# FinalPCBLayoutPoV.net
KiCad netlist of a schematic drawn in EAGLE
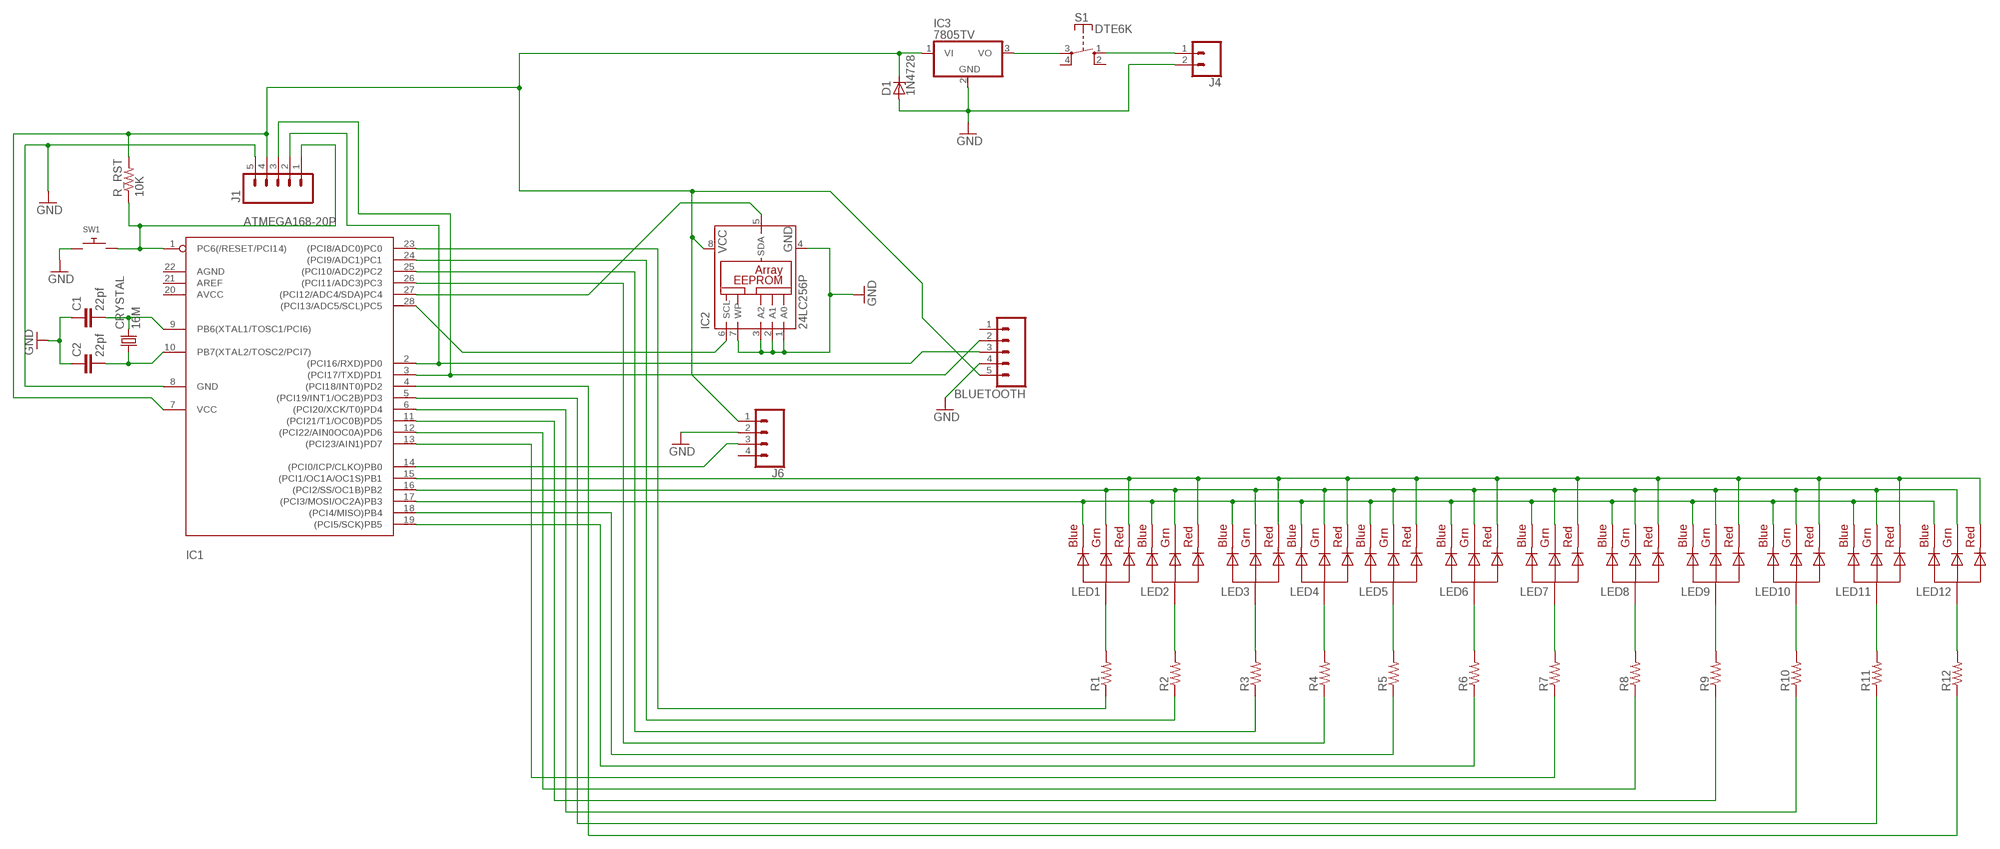
[diagram p0: schematic, sheet 1]

(export (version "E")
  (design (tool "Eeschema 10.0.6"))
  (components
    (comp (ref "BLUETOOTH")
      (value "M05SCREW")
      (footprint "eagle-import:SCREWTERMINAL-3.5MM-5")
      (libsource (lib "eagle-import") (part "M05SCREW"))
    )
    (comp (ref "C1")
      (value "22pf")
      (footprint "eagle-import:C025-060X050")
      (libsource (lib "eagle-import") (part "C-EU025-060X050"))
    )
    (comp (ref "C2")
      (value "22pf")
      (footprint "eagle-import:C025-060X050")
      (libsource (lib "eagle-import") (part "C-EU025-060X050"))
    )
    (comp (ref "CRYSTAL")
      (value "16M")
      (footprint "eagle-import:HC49_S")
      (libsource (lib "eagle-import") (part "CRYSTALHC49S"))
    )
    (comp (ref "D1")
      (value "1N4728")
      (footprint "eagle-import:DO41Z10")
      (libsource (lib "eagle-import") (part "1N4728"))
    )
    (comp (ref "IC1")
      (value "ATMEGA168-20P")
      (footprint "eagle-import:DIL28-3")
      (libsource (lib "eagle-import") (part "ATMEGA168P-20"))
    )
    (comp (ref "IC2")
      (value "24LC256P")
      (footprint "eagle-import:DIL8")
      (fields (field (name "MF") "MICROCHIP") (field (name "MPN") "24LC256-E/P"))
      (libsource (lib "eagle-import") (part "24PLC256"))
    )
    (comp (ref "IC3")
      (value "7805TV")
      (footprint "eagle-import:TO220V")
      (libsource (lib "eagle-import") (part "78TV05"))
    )
    (comp (ref "J1")
      (value "M05SCREW")
      (footprint "eagle-import:SCREWTERMINAL-3.5MM-5")
      (libsource (lib "eagle-import") (part "M05SCREW"))
    )
    (comp (ref "J4")
      (value "CONN_02PTH3")
      (footprint "eagle-import:1X02_LONGPADS")
      (libsource (lib "eagle-import") (part "CONN_02PTH3"))
    )
    (comp (ref "J6")
      (value "CONN_04LONGPADS")
      (footprint "eagle-import:1X04_LONGPADS")
      (libsource (lib "eagle-import") (part "CONN_04LONGPADS"))
    )
    (comp (ref "LED1")
      (value "RGBLED_CA-5MM")
      (footprint "eagle-import:LED5MMRGB")
      (libsource (lib "eagle-import") (part "RGBLED_CA-5MM"))
    )
    (comp (ref "LED2")
      (value "RGBLED_CA-5MM")
      (footprint "eagle-import:LED5MMRGB")
      (libsource (lib "eagle-import") (part "RGBLED_CA-5MM"))
    )
    (comp (ref "LED3")
      (value "RGBLED_CA-5MM")
      (footprint "eagle-import:LED5MMRGB")
      (libsource (lib "eagle-import") (part "RGBLED_CA-5MM"))
    )
    (comp (ref "LED4")
      (value "RGBLED_CA-5MM")
      (footprint "eagle-import:LED5MMRGB")
      (libsource (lib "eagle-import") (part "RGBLED_CA-5MM"))
    )
    (comp (ref "LED5")
      (value "RGBLED_CA-5MM")
      (footprint "eagle-import:LED5MMRGB")
      (libsource (lib "eagle-import") (part "RGBLED_CA-5MM"))
    )
    (comp (ref "LED6")
      (value "RGBLED_CA-5MM")
      (footprint "eagle-import:LED5MMRGB")
      (libsource (lib "eagle-import") (part "RGBLED_CA-5MM"))
    )
    (comp (ref "LED7")
      (value "RGBLED_CA-5MM")
      (footprint "eagle-import:LED5MMRGB")
      (libsource (lib "eagle-import") (part "RGBLED_CA-5MM"))
    )
    (comp (ref "LED8")
      (value "RGBLED_CA-5MM")
      (footprint "eagle-import:LED5MMRGB")
      (libsource (lib "eagle-import") (part "RGBLED_CA-5MM"))
    )
    (comp (ref "LED9")
      (value "RGBLED_CA-5MM")
      (footprint "eagle-import:LED5MMRGB")
      (libsource (lib "eagle-import") (part "RGBLED_CA-5MM"))
    )
    (comp (ref "LED10")
      (value "RGBLED_CA-5MM")
      (footprint "eagle-import:LED5MMRGB")
      (libsource (lib "eagle-import") (part "RGBLED_CA-5MM"))
    )
    (comp (ref "LED11")
      (value "RGBLED_CA-5MM")
      (footprint "eagle-import:LED5MMRGB")
      (libsource (lib "eagle-import") (part "RGBLED_CA-5MM"))
    )
    (comp (ref "LED12")
      (value "RGBLED_CA-5MM")
      (footprint "eagle-import:LED5MMRGB")
      (libsource (lib "eagle-import") (part "RGBLED_CA-5MM"))
    )
    (comp (ref "R1")
      (value "R-US_0207/10")
      (footprint "eagle-import:0207_10")
      (libsource (lib "eagle-import") (part "R-US_0207/10"))
    )
    (comp (ref "R2")
      (value "R-US_0207/10")
      (footprint "eagle-import:0207_10")
      (libsource (lib "eagle-import") (part "R-US_0207/10"))
    )
    (comp (ref "R3")
      (value "R-US_0207/10")
      (footprint "eagle-import:0207_10")
      (libsource (lib "eagle-import") (part "R-US_0207/10"))
    )
    (comp (ref "R4")
      (value "R-US_0207/10")
      (footprint "eagle-import:0207_10")
      (libsource (lib "eagle-import") (part "R-US_0207/10"))
    )
    (comp (ref "R5")
      (value "R-US_0207/10")
      (footprint "eagle-import:0207_10")
      (libsource (lib "eagle-import") (part "R-US_0207/10"))
    )
    (comp (ref "R6")
      (value "R-US_0207/10")
      (footprint "eagle-import:0207_10")
      (libsource (lib "eagle-import") (part "R-US_0207/10"))
    )
    (comp (ref "R7")
      (value "R-US_0207/10")
      (footprint "eagle-import:0207_10")
      (libsource (lib "eagle-import") (part "R-US_0207/10"))
    )
    (comp (ref "R8")
      (value "R-US_0207/10")
      (footprint "eagle-import:0207_10")
      (libsource (lib "eagle-import") (part "R-US_0207/10"))
    )
    (comp (ref "R9")
      (value "R-US_0207/10")
      (footprint "eagle-import:0207_10")
      (libsource (lib "eagle-import") (part "R-US_0207/10"))
    )
    (comp (ref "R10")
      (value "R-US_0207/10")
      (footprint "eagle-import:0207_10")
      (libsource (lib "eagle-import") (part "R-US_0207/10"))
    )
    (comp (ref "R11")
      (value "R-US_0207/10")
      (footprint "eagle-import:0207_10")
      (libsource (lib "eagle-import") (part "R-US_0207/10"))
    )
    (comp (ref "R12")
      (value "R-US_0207/10")
      (footprint "eagle-import:0207_10")
      (libsource (lib "eagle-import") (part "R-US_0207/10"))
    )
    (comp (ref "R_RST")
      (value "10K")
      (footprint "eagle-import:0207_10")
      (libsource (lib "eagle-import") (part "R-US_0207/10"))
    )
    (comp (ref "S1")
      (value "DTE6K")
      (footprint "eagle-import:DTE6K")
      (libsource (lib "eagle-import") (part "DTE6K"))
    )
    (comp (ref "SW1")
      (value "SWITCH_PUSHBUTTONEVQ-PE")
      (footprint "eagle-import:TACT_PANA-EVQ")
      (libsource (lib "eagle-import") (part "SWITCH_PUSHBUTTONEVQ-PE"))
    )
  )
  (nets
    (net (code "1") (name "GND") (class "Default")
      (node (ref "BLUETOOTH") (pin "4") (pinfunction "4_4") (pintype "passive"))
      (node (ref "C1") (pin "1") (pinfunction "1_1") (pintype "passive"))
      (node (ref "C2") (pin "1") (pinfunction "1_1") (pintype "passive"))
      (node (ref "D1") (pin "A") (pinfunction "A_A") (pintype "passive"))
      (node (ref "IC1") (pin "8") (pinfunction "GND_8") (pintype "bidirectional"))
      (node (ref "IC2") (pin "1") (pinfunction "A0_1") (pintype "input"))
      (node (ref "IC2") (pin "2") (pinfunction "A1_2") (pintype "input"))
      (node (ref "IC2") (pin "3") (pinfunction "A2_3") (pintype "input"))
      (node (ref "IC2") (pin "4") (pinfunction "GND_4") (pintype "power_in"))
      (node (ref "IC2") (pin "7") (pinfunction "WP_7") (pintype "input"))
      (node (ref "IC3") (pin "2") (pinfunction "GND_2") (pintype "passive"))
      (node (ref "J1") (pin "5") (pinfunction "5_5") (pintype "passive"))
      (node (ref "J4") (pin "2") (pinfunction "2_2") (pintype "passive"))
      (node (ref "J6") (pin "2") (pinfunction "2_2") (pintype "passive"))
      (node (ref "SW1") (pin "P$1") (pinfunction "P$1_P$1") (pintype "passive"))
    )
    (net (code "2") (name "Net-(IC1-(PCI0{slash}ICP{slash}CLKO)PB0)") (class "Default")
      (node (ref "IC1") (pin "14") (pinfunction "(PCI0/ICP/CLKO)PB0_14") (pintype "bidirectional"))
      (node (ref "J6") (pin "3") (pinfunction "3_3") (pintype "passive"))
    )
    (net (code "3") (name "Net-(IC1-(PCI1{slash}OC1A{slash}OC1S)PB1)") (class "Default")
      (node (ref "IC1") (pin "15") (pinfunction "(PCI1/OC1A/OC1S)PB1_15") (pintype "bidirectional"))
      (node (ref "LED1") (pin "1") (pinfunction "RED_1") (pintype "bidirectional"))
      (node (ref "LED10") (pin "1") (pinfunction "RED_1") (pintype "bidirectional"))
      (node (ref "LED11") (pin "1") (pinfunction "RED_1") (pintype "bidirectional"))
      (node (ref "LED12") (pin "1") (pinfunction "RED_1") (pintype "bidirectional"))
      (node (ref "LED2") (pin "1") (pinfunction "RED_1") (pintype "bidirectional"))
      (node (ref "LED3") (pin "1") (pinfunction "RED_1") (pintype "bidirectional"))
      (node (ref "LED4") (pin "1") (pinfunction "RED_1") (pintype "bidirectional"))
      (node (ref "LED5") (pin "1") (pinfunction "RED_1") (pintype "bidirectional"))
      (node (ref "LED6") (pin "1") (pinfunction "RED_1") (pintype "bidirectional"))
      (node (ref "LED7") (pin "1") (pinfunction "RED_1") (pintype "bidirectional"))
      (node (ref "LED8") (pin "1") (pinfunction "RED_1") (pintype "bidirectional"))
      (node (ref "LED9") (pin "1") (pinfunction "RED_1") (pintype "bidirectional"))
    )
    (net (code "4") (name "Net-(IC1-(PCI2{slash}SS{slash}OC1B)PB2)") (class "Default")
      (node (ref "IC1") (pin "16") (pinfunction "(PCI2/SS/OC1B)PB2_16") (pintype "bidirectional"))
      (node (ref "LED1") (pin "3") (pinfunction "GREEN_3") (pintype "bidirectional"))
      (node (ref "LED10") (pin "3") (pinfunction "GREEN_3") (pintype "bidirectional"))
      (node (ref "LED11") (pin "3") (pinfunction "GREEN_3") (pintype "bidirectional"))
      (node (ref "LED12") (pin "3") (pinfunction "GREEN_3") (pintype "bidirectional"))
      (node (ref "LED2") (pin "3") (pinfunction "GREEN_3") (pintype "bidirectional"))
      (node (ref "LED3") (pin "3") (pinfunction "GREEN_3") (pintype "bidirectional"))
      (node (ref "LED4") (pin "3") (pinfunction "GREEN_3") (pintype "bidirectional"))
      (node (ref "LED5") (pin "3") (pinfunction "GREEN_3") (pintype "bidirectional"))
      (node (ref "LED6") (pin "3") (pinfunction "GREEN_3") (pintype "bidirectional"))
      (node (ref "LED7") (pin "3") (pinfunction "GREEN_3") (pintype "bidirectional"))
      (node (ref "LED8") (pin "3") (pinfunction "GREEN_3") (pintype "bidirectional"))
      (node (ref "LED9") (pin "3") (pinfunction "GREEN_3") (pintype "bidirectional"))
    )
    (net (code "5") (name "Net-(IC1-(PCI3{slash}MOSI{slash}OC2A)PB3)") (class "Default")
      (node (ref "IC1") (pin "17") (pinfunction "(PCI3/MOSI/OC2A)PB3_17") (pintype "bidirectional"))
      (node (ref "LED1") (pin "4") (pinfunction "BLUE_4") (pintype "bidirectional"))
      (node (ref "LED10") (pin "4") (pinfunction "BLUE_4") (pintype "bidirectional"))
      (node (ref "LED11") (pin "4") (pinfunction "BLUE_4") (pintype "bidirectional"))
      (node (ref "LED12") (pin "4") (pinfunction "BLUE_4") (pintype "bidirectional"))
      (node (ref "LED2") (pin "4") (pinfunction "BLUE_4") (pintype "bidirectional"))
      (node (ref "LED3") (pin "4") (pinfunction "BLUE_4") (pintype "bidirectional"))
      (node (ref "LED4") (pin "4") (pinfunction "BLUE_4") (pintype "bidirectional"))
      (node (ref "LED5") (pin "4") (pinfunction "BLUE_4") (pintype "bidirectional"))
      (node (ref "LED6") (pin "4") (pinfunction "BLUE_4") (pintype "bidirectional"))
      (node (ref "LED7") (pin "4") (pinfunction "BLUE_4") (pintype "bidirectional"))
      (node (ref "LED8") (pin "4") (pinfunction "BLUE_4") (pintype "bidirectional"))
      (node (ref "LED9") (pin "4") (pinfunction "BLUE_4") (pintype "bidirectional"))
    )
    (net (code "6") (name "Net-(IC1-(PCI4{slash}MISO)PB4)") (class "Default")
      (node (ref "IC1") (pin "18") (pinfunction "(PCI4/MISO)PB4_18") (pintype "bidirectional"))
      (node (ref "R5") (pin "1") (pinfunction "1_1") (pintype "passive"))
    )
    (net (code "7") (name "Net-(IC1-(PCI5{slash}SCK)PB5)") (class "Default")
      (node (ref "IC1") (pin "19") (pinfunction "(PCI5/SCK)PB5_19") (pintype "bidirectional"))
      (node (ref "R6") (pin "1") (pinfunction "1_1") (pintype "passive"))
    )
    (net (code "8") (name "Net-(IC1-(PCI8{slash}ADC0)PC0)") (class "Default")
      (node (ref "IC1") (pin "23") (pinfunction "(PCI8/ADC0)PC0_23") (pintype "bidirectional"))
      (node (ref "R1") (pin "1") (pinfunction "1_1") (pintype "passive"))
    )
    (net (code "9") (name "Net-(IC1-(PCI9{slash}ADC1)PC1)") (class "Default")
      (node (ref "IC1") (pin "24") (pinfunction "(PCI9/ADC1)PC1_24") (pintype "bidirectional"))
      (node (ref "R2") (pin "1") (pinfunction "1_1") (pintype "passive"))
    )
    (net (code "10") (name "Net-(IC1-(PCI10{slash}ADC2)PC2)") (class "Default")
      (node (ref "IC1") (pin "25") (pinfunction "(PCI10/ADC2)PC2_25") (pintype "bidirectional"))
      (node (ref "R3") (pin "1") (pinfunction "1_1") (pintype "passive"))
    )
    (net (code "11") (name "Net-(IC1-(PCI11{slash}ADC3)PC3)") (class "Default")
      (node (ref "IC1") (pin "26") (pinfunction "(PCI11/ADC3)PC3_26") (pintype "bidirectional"))
      (node (ref "R4") (pin "1") (pinfunction "1_1") (pintype "passive"))
    )
    (net (code "12") (name "Net-(IC1-(PCI12{slash}ADC4{slash}SDA)PC4)") (class "Default")
      (node (ref "IC1") (pin "27") (pinfunction "(PCI12/ADC4/SDA)PC4_27") (pintype "bidirectional"))
      (node (ref "IC2") (pin "5") (pinfunction "SDA_5") (pintype "bidirectional"))
    )
    (net (code "13") (name "Net-(IC1-(PCI13{slash}ADC5{slash}SCL)PC5)") (class "Default")
      (node (ref "IC1") (pin "28") (pinfunction "(PCI13/ADC5/SCL)PC5_28") (pintype "bidirectional"))
      (node (ref "IC2") (pin "6") (pinfunction "SCL_6") (pintype "input"))
    )
    (net (code "14") (name "Net-(IC1-(PCI16{slash}RXD)PD0)") (class "Default")
      (node (ref "BLUETOOTH") (pin "3") (pinfunction "3_3") (pintype "passive"))
      (node (ref "IC1") (pin "2") (pinfunction "(PCI16/RXD)PD0_2") (pintype "bidirectional"))
      (node (ref "J1") (pin "2") (pinfunction "2_2") (pintype "passive"))
    )
    (net (code "15") (name "Net-(IC1-(PCI17{slash}TXD)PD1)") (class "Default")
      (node (ref "BLUETOOTH") (pin "2") (pinfunction "2_2") (pintype "passive"))
      (node (ref "IC1") (pin "3") (pinfunction "(PCI17/TXD)PD1_3") (pintype "bidirectional"))
      (node (ref "J1") (pin "3") (pinfunction "3_3") (pintype "passive"))
    )
    (net (code "16") (name "Net-(IC1-(PCI18{slash}INT0)PD2)") (class "Default")
      (node (ref "IC1") (pin "4") (pinfunction "(PCI18/INT0)PD2_4") (pintype "bidirectional"))
      (node (ref "R12") (pin "1") (pinfunction "1_1") (pintype "passive"))
    )
    (net (code "17") (name "Net-(IC1-(PCI19{slash}INT1{slash}OC2B)PD3)") (class "Default")
      (node (ref "IC1") (pin "5") (pinfunction "(PCI19/INT1/OC2B)PD3_5") (pintype "bidirectional"))
      (node (ref "R11") (pin "1") (pinfunction "1_1") (pintype "passive"))
    )
    (net (code "18") (name "Net-(IC1-(PCI20{slash}XCK{slash}T0)PD4)") (class "Default")
      (node (ref "IC1") (pin "6") (pinfunction "(PCI20/XCK/T0)PD4_6") (pintype "bidirectional"))
      (node (ref "R10") (pin "1") (pinfunction "1_1") (pintype "passive"))
    )
    (net (code "19") (name "Net-(IC1-(PCI21{slash}T1{slash}OC0B)PD5)") (class "Default")
      (node (ref "IC1") (pin "11") (pinfunction "(PCI21/T1/OC0B)PD5_11") (pintype "bidirectional"))
      (node (ref "R9") (pin "1") (pinfunction "1_1") (pintype "passive"))
    )
    (net (code "20") (name "Net-(IC1-(PCI22{slash}AIN0OC0A)PD6)") (class "Default")
      (node (ref "IC1") (pin "12") (pinfunction "(PCI22/AIN0OC0A)PD6_12") (pintype "bidirectional"))
      (node (ref "R8") (pin "1") (pinfunction "1_1") (pintype "passive"))
    )
    (net (code "21") (name "Net-(IC1-(PCI23{slash}AIN1)PD7)") (class "Default")
      (node (ref "IC1") (pin "13") (pinfunction "(PCI23/AIN1)PD7_13") (pintype "bidirectional"))
      (node (ref "R7") (pin "1") (pinfunction "1_1") (pintype "passive"))
    )
    (net (code "22") (name "Net-(IC1-PB6(XTAL1{slash}TOSC1{slash}PCI6))") (class "Default")
      (node (ref "C1") (pin "2") (pinfunction "2_2") (pintype "passive"))
      (node (ref "CRYSTAL") (pin "2") (pinfunction "2_2") (pintype "passive"))
      (node (ref "IC1") (pin "9") (pinfunction "PB6(XTAL1/TOSC1/PCI6)_9") (pintype "bidirectional"))
    )
    (net (code "23") (name "Net-(IC1-PB7(XTAL2{slash}TOSC2{slash}PCI7))") (class "Default")
      (node (ref "C2") (pin "2") (pinfunction "2_2") (pintype "passive"))
      (node (ref "CRYSTAL") (pin "1") (pinfunction "1_1") (pintype "passive"))
      (node (ref "IC1") (pin "10") (pinfunction "PB7(XTAL2/TOSC2/PCI7)_10") (pintype "bidirectional"))
    )
    (net (code "24") (name "Net-(IC1-PC6({slash}RESET{slash}PCI14))") (class "Default")
      (node (ref "IC1") (pin "1") (pinfunction "PC6(/RESET/PCI14)_1") (pintype "bidirectional"))
      (node (ref "J1") (pin "1") (pinfunction "1_1") (pintype "passive"))
      (node (ref "R_RST") (pin "1") (pinfunction "1_1") (pintype "passive"))
      (node (ref "SW1") (pin "P$2") (pinfunction "P$2_P$2") (pintype "passive"))
    )
    (net (code "25") (name "Net-(IC1-VCC)") (class "Default")
      (node (ref "BLUETOOTH") (pin "5") (pinfunction "5_5") (pintype "passive"))
      (node (ref "D1") (pin "C") (pinfunction "C_C") (pintype "passive"))
      (node (ref "IC1") (pin "7") (pinfunction "VCC_7") (pintype "bidirectional"))
      (node (ref "IC2") (pin "8") (pinfunction "VCC_8") (pintype "power_in"))
      (node (ref "IC3") (pin "1") (pinfunction "VI_1") (pintype "input"))
      (node (ref "J1") (pin "4") (pinfunction "4_4") (pintype "passive"))
      (node (ref "J6") (pin "1") (pinfunction "1_1") (pintype "passive"))
      (node (ref "R_RST") (pin "2") (pinfunction "2_2") (pintype "passive"))
    )
    (net (code "26") (name "Net-(IC3-VO)") (class "Default")
      (node (ref "IC3") (pin "3") (pinfunction "VO_3") (pintype "passive"))
      (node (ref "S1") (pin "3") (pinfunction "P_3") (pintype "passive"))
    )
    (net (code "27") (name "Net-(J4-Pad1)") (class "Default")
      (node (ref "J4") (pin "1") (pinfunction "1_1") (pintype "passive"))
      (node (ref "S1") (pin "1") (pinfunction "S_1") (pintype "passive"))
    )
    (net (code "28") (name "Net-(LED1-VCC)") (class "Default")
      (node (ref "LED1") (pin "2") (pinfunction "VCC_2") (pintype "bidirectional"))
      (node (ref "R1") (pin "2") (pinfunction "2_2") (pintype "passive"))
    )
    (net (code "29") (name "Net-(LED2-VCC)") (class "Default")
      (node (ref "LED2") (pin "2") (pinfunction "VCC_2") (pintype "bidirectional"))
      (node (ref "R2") (pin "2") (pinfunction "2_2") (pintype "passive"))
    )
    (net (code "30") (name "Net-(LED3-VCC)") (class "Default")
      (node (ref "LED3") (pin "2") (pinfunction "VCC_2") (pintype "bidirectional"))
      (node (ref "R3") (pin "2") (pinfunction "2_2") (pintype "passive"))
    )
    (net (code "31") (name "Net-(LED4-VCC)") (class "Default")
      (node (ref "LED4") (pin "2") (pinfunction "VCC_2") (pintype "bidirectional"))
      (node (ref "R4") (pin "2") (pinfunction "2_2") (pintype "passive"))
    )
    (net (code "32") (name "Net-(LED5-VCC)") (class "Default")
      (node (ref "LED5") (pin "2") (pinfunction "VCC_2") (pintype "bidirectional"))
      (node (ref "R5") (pin "2") (pinfunction "2_2") (pintype "passive"))
    )
    (net (code "33") (name "Net-(LED6-VCC)") (class "Default")
      (node (ref "LED6") (pin "2") (pinfunction "VCC_2") (pintype "bidirectional"))
      (node (ref "R6") (pin "2") (pinfunction "2_2") (pintype "passive"))
    )
    (net (code "34") (name "Net-(LED7-VCC)") (class "Default")
      (node (ref "LED7") (pin "2") (pinfunction "VCC_2") (pintype "bidirectional"))
      (node (ref "R7") (pin "2") (pinfunction "2_2") (pintype "passive"))
    )
    (net (code "35") (name "Net-(LED8-VCC)") (class "Default")
      (node (ref "LED8") (pin "2") (pinfunction "VCC_2") (pintype "bidirectional"))
      (node (ref "R8") (pin "2") (pinfunction "2_2") (pintype "passive"))
    )
    (net (code "36") (name "Net-(LED9-VCC)") (class "Default")
      (node (ref "LED9") (pin "2") (pinfunction "VCC_2") (pintype "bidirectional"))
      (node (ref "R9") (pin "2") (pinfunction "2_2") (pintype "passive"))
    )
    (net (code "37") (name "Net-(LED10-VCC)") (class "Default")
      (node (ref "LED10") (pin "2") (pinfunction "VCC_2") (pintype "bidirectional"))
      (node (ref "R10") (pin "2") (pinfunction "2_2") (pintype "passive"))
    )
    (net (code "38") (name "Net-(LED11-VCC)") (class "Default")
      (node (ref "LED11") (pin "2") (pinfunction "VCC_2") (pintype "bidirectional"))
      (node (ref "R11") (pin "2") (pinfunction "2_2") (pintype "passive"))
    )
    (net (code "39") (name "Net-(LED12-VCC)") (class "Default")
      (node (ref "LED12") (pin "2") (pinfunction "VCC_2") (pintype "bidirectional"))
      (node (ref "R12") (pin "2") (pinfunction "2_2") (pintype "passive"))
    )
    (net (code "40") (name "unconnected-(BLUETOOTH-Pad1)") (class "Default")
      (node (ref "BLUETOOTH") (pin "1") (pinfunction "1_1") (pintype "passive"))
    )
    (net (code "41") (name "unconnected-(IC1-AGND-Pad22)") (class "Default")
      (node (ref "IC1") (pin "22") (pinfunction "AGND_22") (pintype "bidirectional"))
    )
    (net (code "42") (name "unconnected-(IC1-AREF-Pad21)") (class "Default")
      (node (ref "IC1") (pin "21") (pinfunction "AREF_21") (pintype "bidirectional"))
    )
    (net (code "43") (name "unconnected-(IC1-AVCC-Pad20)") (class "Default")
      (node (ref "IC1") (pin "20") (pinfunction "AVCC_20") (pintype "bidirectional"))
    )
    (net (code "44") (name "unconnected-(J6-Pad4)") (class "Default")
      (node (ref "J6") (pin "4") (pinfunction "4_4") (pintype "passive"))
    )
    (net (code "45") (name "unconnected-(S1-P-Pad4)") (class "Default")
      (node (ref "S1") (pin "4") (pinfunction "P_4") (pintype "passive"))
    )
    (net (code "46") (name "unconnected-(S1-S-Pad2)") (class "Default")
      (node (ref "S1") (pin "2") (pinfunction "S_2") (pintype "passive"))
    )
  )
)
